# axiom_beta_plugin_module_1xHDMI_v0_6_556.net
KiCad netlist of a schematic drawn in EAGLE
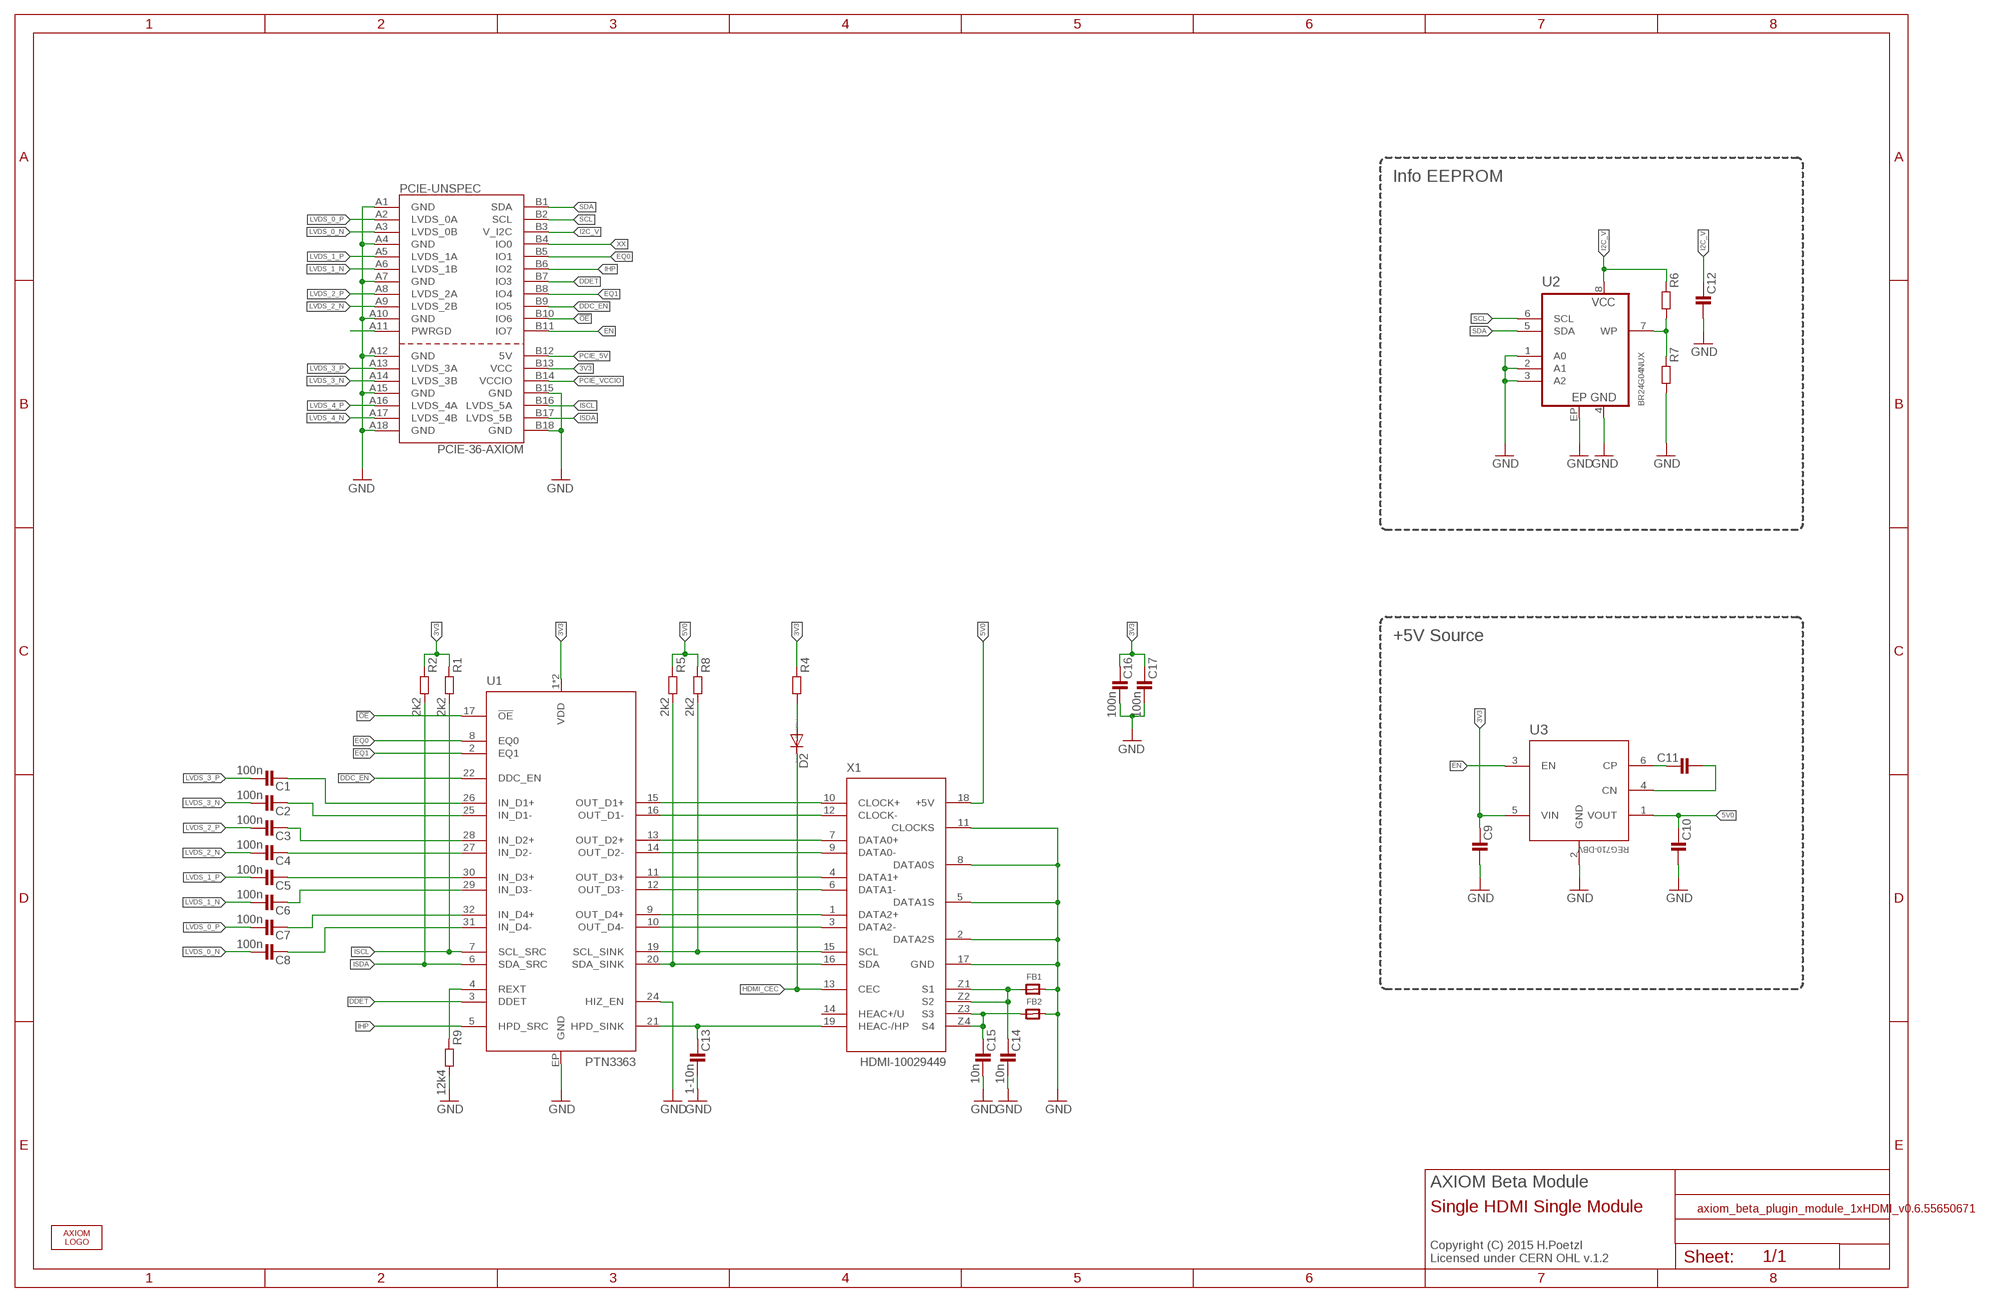
[diagram p0: schematic, sheet 1]

(export (version "E")
  (design (tool "Eeschema 10.0.6"))
  (components
    (comp (ref "C1")
      (value "100n")
      (footprint "eagle-import:0402-C")
      (libsource (lib "eagle-import") (part "C0402-C"))
    )
    (comp (ref "C2")
      (value "100n")
      (footprint "eagle-import:0402-C")
      (libsource (lib "eagle-import") (part "C0402-C"))
    )
    (comp (ref "C3")
      (value "100n")
      (footprint "eagle-import:0402-C")
      (libsource (lib "eagle-import") (part "C0402-C"))
    )
    (comp (ref "C4")
      (value "100n")
      (footprint "eagle-import:0402-C")
      (libsource (lib "eagle-import") (part "C0402-C"))
    )
    (comp (ref "C5")
      (value "100n")
      (footprint "eagle-import:0402-C")
      (libsource (lib "eagle-import") (part "C0402-C"))
    )
    (comp (ref "C6")
      (value "100n")
      (footprint "eagle-import:0402-C")
      (libsource (lib "eagle-import") (part "C0402-C"))
    )
    (comp (ref "C7")
      (value "100n")
      (footprint "eagle-import:0402-C")
      (libsource (lib "eagle-import") (part "C0402-C"))
    )
    (comp (ref "C8")
      (value "100n")
      (footprint "eagle-import:0402-C")
      (libsource (lib "eagle-import") (part "C0402-C"))
    )
    (comp (ref "C9")
      (value "C0603-B")
      (footprint "eagle-import:0603-B")
      (libsource (lib "eagle-import") (part "C0603-B"))
    )
    (comp (ref "C10")
      (value "C0603-B")
      (footprint "eagle-import:0603-B")
      (libsource (lib "eagle-import") (part "C0603-B"))
    )
    (comp (ref "C11")
      (value "C0603-B")
      (footprint "eagle-import:0603-B")
      (libsource (lib "eagle-import") (part "C0603-B"))
    )
    (comp (ref "C12")
      (value "C0402-B")
      (footprint "eagle-import:0402-B")
      (libsource (lib "eagle-import") (part "C0402-B"))
    )
    (comp (ref "C13")
      (value "1-10n")
      (footprint "eagle-import:0402-B")
      (libsource (lib "eagle-import") (part "C0402-B"))
    )
    (comp (ref "C14")
      (value "10n")
      (footprint "eagle-import:0402-B")
      (libsource (lib "eagle-import") (part "C0402-B"))
    )
    (comp (ref "C15")
      (value "10n")
      (footprint "eagle-import:0402-B")
      (libsource (lib "eagle-import") (part "C0402-B"))
    )
    (comp (ref "C16")
      (value "100n")
      (footprint "eagle-import:0402-B")
      (libsource (lib "eagle-import") (part "C0402-B"))
    )
    (comp (ref "C17")
      (value "100n")
      (footprint "eagle-import:0402-B")
      (libsource (lib "eagle-import") (part "C0402-B"))
    )
    (comp (ref "D2")
      (value "DIODE-SOD523")
      (footprint "eagle-import:SOD523")
      (libsource (lib "eagle-import") (part "DIODE-SOD523"))
    )
    (comp (ref "FB1")
      (value "FERRITE_0603MP")
      (footprint "eagle-import:_0603MP")
      (libsource (lib "eagle-import") (part "FERRITE_0603MP"))
    )
    (comp (ref "FB2")
      (value "FERRITE_0603MP")
      (footprint "eagle-import:_0603MP")
      (libsource (lib "eagle-import") (part "FERRITE_0603MP"))
    )
    (comp (ref "PCIE-UNSPEC")
      (value "PCIE-36-AXIOM")
      (footprint "eagle-import:PCIE-36-AXIOM")
      (libsource (lib "eagle-import") (part "PCIE-36-AXIOM"))
    )
    (comp (ref "R1")
      (value "2k2")
      (footprint "eagle-import:0402-B")
      (libsource (lib "eagle-import") (part "R0402-B"))
    )
    (comp (ref "R2")
      (value "2k2")
      (footprint "eagle-import:0402-B")
      (libsource (lib "eagle-import") (part "R0402-B"))
    )
    (comp (ref "R4")
      (value "R0402-B")
      (footprint "eagle-import:0402-B")
      (libsource (lib "eagle-import") (part "R0402-B"))
    )
    (comp (ref "R5")
      (value "2k2")
      (footprint "eagle-import:0402-B")
      (libsource (lib "eagle-import") (part "R0402-B"))
    )
    (comp (ref "R6")
      (value "R0402-B")
      (footprint "eagle-import:0402-B")
      (libsource (lib "eagle-import") (part "R0402-B"))
    )
    (comp (ref "R7")
      (value "R0402-B")
      (footprint "eagle-import:0402-B")
      (libsource (lib "eagle-import") (part "R0402-B"))
    )
    (comp (ref "R8")
      (value "2k2")
      (footprint "eagle-import:0402-B")
      (libsource (lib "eagle-import") (part "R0402-B"))
    )
    (comp (ref "R9")
      (value "12k4")
      (footprint "eagle-import:0402-B")
      (libsource (lib "eagle-import") (part "R0402-B"))
    )
    (comp (ref "U$1")
      (value "AXIOM_LOGO459X70")
      (footprint "eagle-import:AXIOM_LOGO_459X70")
      (libsource (lib "eagle-import") (part "AXIOM_LOGO459X70"))
    )
    (comp (ref "U1")
      (value "PTN3363")
      (footprint "eagle-import:HVQFN32")
      (libsource (lib "eagle-import") (part "PTN3363"))
    )
    (comp (ref "U2")
      (value "BR24G04NUX")
      (footprint "eagle-import:DFN200X300X100-9N")
      (libsource (lib "eagle-import") (part "BR24G04NUX"))
    )
    (comp (ref "U3")
      (value "REG710-DBV")
      (footprint "eagle-import:DBV")
      (libsource (lib "eagle-import") (part "REG710-DBV"))
    )
    (comp (ref "X1")
      (value "HDMI-10029449")
      (footprint "eagle-import:10029449-X01XLF")
      (libsource (lib "eagle-import") (part "HDMI-10029449"))
    )
  )
  (nets
    (net (code "1") (name "/~{OE}") (class "Default")
      (node (ref "PCIE-UNSPEC") (pin "B10") (pinfunction "IO6_B10") (pintype "passive"))
      (node (ref "U1") (pin "17") (pinfunction "~{OE}_17") (pintype "bidirectional"))
    )
    (net (code "2") (name "3V3") (class "Default")
      (node (ref "C16") (pin "1") (pinfunction "1_1") (pintype "passive"))
      (node (ref "C17") (pin "1") (pinfunction "1_1") (pintype "passive"))
      (node (ref "C9") (pin "1") (pinfunction "1_1") (pintype "passive"))
      (node (ref "PCIE-UNSPEC") (pin "B13") (pinfunction "VCC_B13") (pintype "passive"))
      (node (ref "R1") (pin "1") (pinfunction "1_1") (pintype "passive"))
      (node (ref "R2") (pin "1") (pinfunction "1_1") (pintype "passive"))
      (node (ref "R4") (pin "1") (pinfunction "1_1") (pintype "passive"))
      (node (ref "U1") (pin "1") (pinfunction "VDD_1") (pintype "power_in"))
      (node (ref "U1") (pin "18") (pinfunction "VDD_18") (pintype "power_in"))
      (node (ref "U3") (pin "5") (pinfunction "VIN_5") (pintype "power_in"))
    )
    (net (code "3") (name "5V0") (class "Default")
      (node (ref "C10") (pin "1") (pinfunction "1_1") (pintype "passive"))
      (node (ref "R5") (pin "1") (pinfunction "1_1") (pintype "passive"))
      (node (ref "R8") (pin "1") (pinfunction "1_1") (pintype "passive"))
      (node (ref "U3") (pin "1") (pinfunction "VOUT_1") (pintype "output"))
      (node (ref "X1") (pin "18") (pinfunction "+5V_18") (pintype "power_in"))
    )
    (net (code "4") (name "DDC_EN") (class "Default")
      (node (ref "PCIE-UNSPEC") (pin "B9") (pinfunction "IO5_B9") (pintype "passive"))
      (node (ref "U1") (pin "22") (pinfunction "DDC_EN_22") (pintype "bidirectional"))
    )
    (net (code "5") (name "DDET") (class "Default")
      (node (ref "PCIE-UNSPEC") (pin "B7") (pinfunction "IO3_B7") (pintype "passive"))
      (node (ref "U1") (pin "3") (pinfunction "DDET_3") (pintype "bidirectional"))
    )
    (net (code "6") (name "EN") (class "Default")
      (node (ref "PCIE-UNSPEC") (pin "B11") (pinfunction "IO7_B11") (pintype "passive"))
      (node (ref "U3") (pin "3") (pinfunction "EN_3") (pintype "input"))
    )
    (net (code "7") (name "EQ0") (class "Default")
      (node (ref "PCIE-UNSPEC") (pin "B5") (pinfunction "IO1_B5") (pintype "passive"))
      (node (ref "U1") (pin "8") (pinfunction "EQ0_8") (pintype "bidirectional"))
    )
    (net (code "8") (name "EQ1") (class "Default")
      (node (ref "PCIE-UNSPEC") (pin "B8") (pinfunction "IO4_B8") (pintype "passive"))
      (node (ref "U1") (pin "2") (pinfunction "EQ1_2") (pintype "bidirectional"))
    )
    (net (code "9") (name "GND") (class "Default")
      (node (ref "C10") (pin "2") (pinfunction "2_2") (pintype "passive"))
      (node (ref "C12") (pin "2") (pinfunction "2_2") (pintype "passive"))
      (node (ref "C13") (pin "2") (pinfunction "2_2") (pintype "passive"))
      (node (ref "C14") (pin "2") (pinfunction "2_2") (pintype "passive"))
      (node (ref "C15") (pin "2") (pinfunction "2_2") (pintype "passive"))
      (node (ref "C16") (pin "2") (pinfunction "2_2") (pintype "passive"))
      (node (ref "C17") (pin "2") (pinfunction "2_2") (pintype "passive"))
      (node (ref "C9") (pin "2") (pinfunction "2_2") (pintype "passive"))
      (node (ref "FB1") (pin "2") (pinfunction "P$2_2") (pintype "passive"))
      (node (ref "FB2") (pin "2") (pinfunction "P$2_2") (pintype "passive"))
      (node (ref "PCIE-UNSPEC") (pin "A1") (pinfunction "GND_A1") (pintype "passive"))
      (node (ref "PCIE-UNSPEC") (pin "A10") (pinfunction "GND_A10") (pintype "passive"))
      (node (ref "PCIE-UNSPEC") (pin "A12") (pinfunction "GND_A12") (pintype "passive"))
      (node (ref "PCIE-UNSPEC") (pin "A15") (pinfunction "GND_A15") (pintype "passive"))
      (node (ref "PCIE-UNSPEC") (pin "A18") (pinfunction "GND_A18") (pintype "passive"))
      (node (ref "PCIE-UNSPEC") (pin "A4") (pinfunction "GND_A4") (pintype "passive"))
      (node (ref "PCIE-UNSPEC") (pin "A7") (pinfunction "GND_A7") (pintype "passive"))
      (node (ref "PCIE-UNSPEC") (pin "B15") (pinfunction "GND_B15") (pintype "passive"))
      (node (ref "PCIE-UNSPEC") (pin "B18") (pinfunction "GND_B18") (pintype "passive"))
      (node (ref "R7") (pin "2") (pinfunction "2_2") (pintype "passive"))
      (node (ref "R9") (pin "2") (pinfunction "2_2") (pintype "passive"))
      (node (ref "U1") (pin "24") (pinfunction "HIZ_EN_24") (pintype "bidirectional"))
      (node (ref "U1") (pin "EP") (pinfunction "GND_EP") (pintype "bidirectional"))
      (node (ref "U2") (pin "1") (pinfunction "A0_1") (pintype "input"))
      (node (ref "U2") (pin "2") (pinfunction "A1_2") (pintype "input"))
      (node (ref "U2") (pin "3") (pinfunction "A2_3") (pintype "input"))
      (node (ref "U2") (pin "4") (pinfunction "GND_4") (pintype "passive"))
      (node (ref "U2") (pin "EP") (pinfunction "EP_EP") (pintype "passive"))
      (node (ref "U3") (pin "2") (pinfunction "GND_2") (pintype "passive"))
      (node (ref "X1") (pin "11") (pinfunction "CLOCKS_11") (pintype "power_in"))
      (node (ref "X1") (pin "17") (pinfunction "GND_17") (pintype "bidirectional"))
      (node (ref "X1") (pin "2") (pinfunction "DATA2S_2") (pintype "power_in"))
      (node (ref "X1") (pin "5") (pinfunction "DATA1S_5") (pintype "power_in"))
      (node (ref "X1") (pin "8") (pinfunction "DATA0S_8") (pintype "power_in"))
    )
    (net (code "10") (name "HDMI_CEC") (class "Default")
      (node (ref "D2") (pin "C") (pinfunction "C_C") (pintype "passive"))
      (node (ref "X1") (pin "13") (pinfunction "CEC_13") (pintype "bidirectional"))
    )
    (net (code "11") (name "I2C_V") (class "Default")
      (node (ref "C12") (pin "1") (pinfunction "1_1") (pintype "passive"))
      (node (ref "PCIE-UNSPEC") (pin "B3") (pinfunction "V_I2C_B3") (pintype "passive"))
      (node (ref "R6") (pin "1") (pinfunction "1_1") (pintype "passive"))
      (node (ref "U2") (pin "8") (pinfunction "VCC_8") (pintype "power_in"))
    )
    (net (code "12") (name "IHP") (class "Default")
      (node (ref "PCIE-UNSPEC") (pin "B6") (pinfunction "IO2_B6") (pintype "passive"))
      (node (ref "U1") (pin "5") (pinfunction "HPD_SRC_5") (pintype "bidirectional"))
    )
    (net (code "13") (name "ISCL") (class "Default")
      (node (ref "PCIE-UNSPEC") (pin "B16") (pinfunction "LVDS_5A_B16") (pintype "passive"))
      (node (ref "R1") (pin "2") (pinfunction "2_2") (pintype "passive"))
      (node (ref "U1") (pin "7") (pinfunction "SCL_SRC_7") (pintype "bidirectional"))
    )
    (net (code "14") (name "ISDA") (class "Default")
      (node (ref "PCIE-UNSPEC") (pin "B17") (pinfunction "LVDS_5B_B17") (pintype "passive"))
      (node (ref "R2") (pin "2") (pinfunction "2_2") (pintype "passive"))
      (node (ref "U1") (pin "6") (pinfunction "SDA_SRC_6") (pintype "bidirectional"))
    )
    (net (code "15") (name "LVDS_0_N") (class "Default")
      (node (ref "C8") (pin "2") (pinfunction "2_2") (pintype "passive"))
      (node (ref "PCIE-UNSPEC") (pin "A3") (pinfunction "LVDS_0B_A3") (pintype "passive"))
    )
    (net (code "16") (name "LVDS_0_P") (class "Default")
      (node (ref "C7") (pin "2") (pinfunction "2_2") (pintype "passive"))
      (node (ref "PCIE-UNSPEC") (pin "A2") (pinfunction "LVDS_0A_A2") (pintype "passive"))
    )
    (net (code "17") (name "LVDS_1_N") (class "Default")
      (node (ref "C6") (pin "2") (pinfunction "2_2") (pintype "passive"))
      (node (ref "PCIE-UNSPEC") (pin "A6") (pinfunction "LVDS_1B_A6") (pintype "passive"))
    )
    (net (code "18") (name "LVDS_1_P") (class "Default")
      (node (ref "C5") (pin "2") (pinfunction "2_2") (pintype "passive"))
      (node (ref "PCIE-UNSPEC") (pin "A5") (pinfunction "LVDS_1A_A5") (pintype "passive"))
    )
    (net (code "19") (name "LVDS_2_N") (class "Default")
      (node (ref "C4") (pin "2") (pinfunction "2_2") (pintype "passive"))
      (node (ref "PCIE-UNSPEC") (pin "A9") (pinfunction "LVDS_2B_A9") (pintype "passive"))
    )
    (net (code "20") (name "LVDS_2_P") (class "Default")
      (node (ref "C3") (pin "2") (pinfunction "2_2") (pintype "passive"))
      (node (ref "PCIE-UNSPEC") (pin "A8") (pinfunction "LVDS_2A_A8") (pintype "passive"))
    )
    (net (code "21") (name "LVDS_3_N") (class "Default")
      (node (ref "C2") (pin "2") (pinfunction "2_2") (pintype "passive"))
      (node (ref "PCIE-UNSPEC") (pin "A14") (pinfunction "LVDS_3B_A14") (pintype "passive"))
    )
    (net (code "22") (name "LVDS_3_P") (class "Default")
      (node (ref "C1") (pin "2") (pinfunction "2_2") (pintype "passive"))
      (node (ref "PCIE-UNSPEC") (pin "A13") (pinfunction "LVDS_3A_A13") (pintype "passive"))
    )
    (net (code "23") (name "LVDS_4_N") (class "Default")
      (node (ref "PCIE-UNSPEC") (pin "A17") (pinfunction "LVDS_4B_A17") (pintype "passive"))
    )
    (net (code "24") (name "LVDS_4_P") (class "Default")
      (node (ref "PCIE-UNSPEC") (pin "A16") (pinfunction "LVDS_4A_A16") (pintype "passive"))
    )
    (net (code "25") (name "Net-(D2-PadA)") (class "Default")
      (node (ref "D2") (pin "A") (pinfunction "A_A") (pintype "passive"))
      (node (ref "R4") (pin "2") (pinfunction "2_2") (pintype "passive"))
    )
    (net (code "26") (name "Net-(FB1-P$1)") (class "Default")
      (node (ref "C14") (pin "1") (pinfunction "1_1") (pintype "passive"))
      (node (ref "FB1") (pin "1") (pinfunction "P$1_1") (pintype "passive"))
      (node (ref "X1") (pin "Z1") (pinfunction "S1_Z1") (pintype "power_in"))
      (node (ref "X1") (pin "Z2") (pinfunction "S2_Z2") (pintype "power_in"))
    )
    (net (code "27") (name "Net-(FB2-P$1)") (class "Default")
      (node (ref "C15") (pin "1") (pinfunction "1_1") (pintype "passive"))
      (node (ref "FB2") (pin "1") (pinfunction "P$1_1") (pintype "passive"))
      (node (ref "X1") (pin "Z3") (pinfunction "S3_Z3") (pintype "power_in"))
      (node (ref "X1") (pin "Z4") (pinfunction "S4_Z4") (pintype "power_in"))
    )
    (net (code "28") (name "Net-(U1-HPD_SINK)") (class "Default")
      (node (ref "C13") (pin "1") (pinfunction "1_1") (pintype "passive"))
      (node (ref "U1") (pin "21") (pinfunction "HPD_SINK_21") (pintype "bidirectional"))
      (node (ref "X1") (pin "19") (pinfunction "HEAC-/HP_19") (pintype "bidirectional"))
    )
    (net (code "29") (name "Net-(U1-IN_D1+)") (class "Default")
      (node (ref "C1") (pin "1") (pinfunction "1_1") (pintype "passive"))
      (node (ref "U1") (pin "26") (pinfunction "IN_D1+_26") (pintype "bidirectional"))
    )
    (net (code "30") (name "Net-(U1-IN_D1-)") (class "Default")
      (node (ref "C2") (pin "1") (pinfunction "1_1") (pintype "passive"))
      (node (ref "U1") (pin "25") (pinfunction "IN_D1-_25") (pintype "bidirectional"))
    )
    (net (code "31") (name "Net-(U1-IN_D2+)") (class "Default")
      (node (ref "C3") (pin "1") (pinfunction "1_1") (pintype "passive"))
      (node (ref "U1") (pin "28") (pinfunction "IN_D2+_28") (pintype "bidirectional"))
    )
    (net (code "32") (name "Net-(U1-IN_D2-)") (class "Default")
      (node (ref "C4") (pin "1") (pinfunction "1_1") (pintype "passive"))
      (node (ref "U1") (pin "27") (pinfunction "IN_D2-_27") (pintype "bidirectional"))
    )
    (net (code "33") (name "Net-(U1-IN_D3+)") (class "Default")
      (node (ref "C5") (pin "1") (pinfunction "1_1") (pintype "passive"))
      (node (ref "U1") (pin "30") (pinfunction "IN_D3+_30") (pintype "bidirectional"))
    )
    (net (code "34") (name "Net-(U1-IN_D3-)") (class "Default")
      (node (ref "C6") (pin "1") (pinfunction "1_1") (pintype "passive"))
      (node (ref "U1") (pin "29") (pinfunction "IN_D3-_29") (pintype "bidirectional"))
    )
    (net (code "35") (name "Net-(U1-IN_D4+)") (class "Default")
      (node (ref "C7") (pin "1") (pinfunction "1_1") (pintype "passive"))
      (node (ref "U1") (pin "32") (pinfunction "IN_D4+_32") (pintype "bidirectional"))
    )
    (net (code "36") (name "Net-(U1-IN_D4-)") (class "Default")
      (node (ref "C8") (pin "1") (pinfunction "1_1") (pintype "passive"))
      (node (ref "U1") (pin "31") (pinfunction "IN_D4-_31") (pintype "bidirectional"))
    )
    (net (code "37") (name "Net-(U1-OUT_D1+)") (class "Default")
      (node (ref "U1") (pin "15") (pinfunction "OUT_D1+_15") (pintype "bidirectional"))
      (node (ref "X1") (pin "10") (pinfunction "CLOCK+_10") (pintype "bidirectional"))
    )
    (net (code "38") (name "Net-(U1-OUT_D1-)") (class "Default")
      (node (ref "U1") (pin "16") (pinfunction "OUT_D1-_16") (pintype "bidirectional"))
      (node (ref "X1") (pin "12") (pinfunction "CLOCK-_12") (pintype "bidirectional"))
    )
    (net (code "39") (name "Net-(U1-OUT_D2+)") (class "Default")
      (node (ref "U1") (pin "13") (pinfunction "OUT_D2+_13") (pintype "bidirectional"))
      (node (ref "X1") (pin "7") (pinfunction "DATA0+_7") (pintype "bidirectional"))
    )
    (net (code "40") (name "Net-(U1-OUT_D2-)") (class "Default")
      (node (ref "U1") (pin "14") (pinfunction "OUT_D2-_14") (pintype "bidirectional"))
      (node (ref "X1") (pin "9") (pinfunction "DATA0-_9") (pintype "bidirectional"))
    )
    (net (code "41") (name "Net-(U1-OUT_D3+)") (class "Default")
      (node (ref "U1") (pin "11") (pinfunction "OUT_D3+_11") (pintype "bidirectional"))
      (node (ref "X1") (pin "4") (pinfunction "DATA1+_4") (pintype "bidirectional"))
    )
    (net (code "42") (name "Net-(U1-OUT_D3-)") (class "Default")
      (node (ref "U1") (pin "12") (pinfunction "OUT_D3-_12") (pintype "bidirectional"))
      (node (ref "X1") (pin "6") (pinfunction "DATA1-_6") (pintype "bidirectional"))
    )
    (net (code "43") (name "Net-(U1-OUT_D4+)") (class "Default")
      (node (ref "U1") (pin "9") (pinfunction "OUT_D4+_9") (pintype "bidirectional"))
      (node (ref "X1") (pin "1") (pinfunction "DATA2+_1") (pintype "bidirectional"))
    )
    (net (code "44") (name "Net-(U1-OUT_D4-)") (class "Default")
      (node (ref "U1") (pin "10") (pinfunction "OUT_D4-_10") (pintype "bidirectional"))
      (node (ref "X1") (pin "3") (pinfunction "DATA2-_3") (pintype "bidirectional"))
    )
    (net (code "45") (name "Net-(U1-REXT)") (class "Default")
      (node (ref "R9") (pin "1") (pinfunction "1_1") (pintype "passive"))
      (node (ref "U1") (pin "4") (pinfunction "REXT_4") (pintype "bidirectional"))
    )
    (net (code "46") (name "Net-(U1-SCL_SINK)") (class "Default")
      (node (ref "R8") (pin "2") (pinfunction "2_2") (pintype "passive"))
      (node (ref "U1") (pin "19") (pinfunction "SCL_SINK_19") (pintype "bidirectional"))
      (node (ref "X1") (pin "15") (pinfunction "SCL_15") (pintype "bidirectional"))
    )
    (net (code "47") (name "Net-(U1-SDA_SINK)") (class "Default")
      (node (ref "R5") (pin "2") (pinfunction "2_2") (pintype "passive"))
      (node (ref "U1") (pin "20") (pinfunction "SDA_SINK_20") (pintype "bidirectional"))
      (node (ref "X1") (pin "16") (pinfunction "SDA_16") (pintype "bidirectional"))
    )
    (net (code "48") (name "Net-(U2-WP)") (class "Default")
      (node (ref "R6") (pin "2") (pinfunction "2_2") (pintype "passive"))
      (node (ref "R7") (pin "1") (pinfunction "1_1") (pintype "passive"))
      (node (ref "U2") (pin "7") (pinfunction "WP_7") (pintype "input"))
    )
    (net (code "49") (name "Net-(U3-CN)") (class "Default")
      (node (ref "C11") (pin "2") (pinfunction "2_2") (pintype "passive"))
      (node (ref "U3") (pin "4") (pinfunction "CN_4") (pintype "power_in"))
    )
    (net (code "50") (name "Net-(U3-CP)") (class "Default")
      (node (ref "C11") (pin "1") (pinfunction "1_1") (pintype "passive"))
      (node (ref "U3") (pin "6") (pinfunction "CP_6") (pintype "output"))
    )
    (net (code "51") (name "PCIE_5V") (class "Default")
      (node (ref "PCIE-UNSPEC") (pin "B12") (pinfunction "5V_B12") (pintype "passive"))
    )
    (net (code "52") (name "PCIE_VCCIO") (class "Default")
      (node (ref "PCIE-UNSPEC") (pin "B14") (pinfunction "VCCIO_B14") (pintype "passive"))
    )
    (net (code "53") (name "SCL") (class "Default")
      (node (ref "PCIE-UNSPEC") (pin "B2") (pinfunction "SCL_B2") (pintype "passive"))
      (node (ref "U2") (pin "6") (pinfunction "SCL_6") (pintype "input"))
    )
    (net (code "54") (name "SDA") (class "Default")
      (node (ref "PCIE-UNSPEC") (pin "B1") (pinfunction "SDA_B1") (pintype "passive"))
      (node (ref "U2") (pin "5") (pinfunction "SDA_5") (pintype "bidirectional"))
    )
    (net (code "55") (name "XX") (class "Default")
      (node (ref "PCIE-UNSPEC") (pin "B4") (pinfunction "IO0_B4") (pintype "passive"))
    )
    (net (code "56") (name "unconnected-(PCIE-UNSPEC-PWRGD-PadA11)") (class "Default")
      (node (ref "PCIE-UNSPEC") (pin "A11") (pinfunction "PWRGD_A11") (pintype "passive"))
    )
    (net (code "57") (name "unconnected-(X1-HEAC+{slash}U-Pad14)") (class "Default")
      (node (ref "X1") (pin "14") (pinfunction "HEAC+/U_14") (pintype "bidirectional"))
    )
  )
)
